# Current-LoadSwitches_3V3.net
KiCad netlist of a schematic drawn in Altium Designer
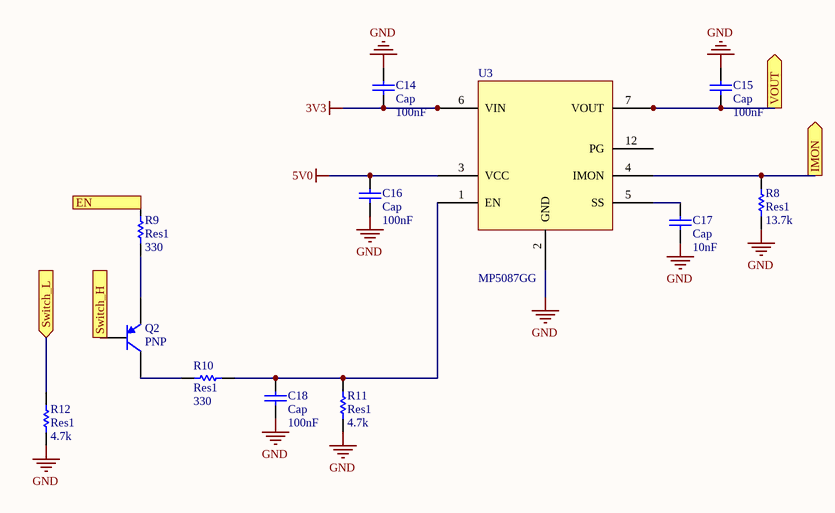
[diagram p0: Current-LoadSwitches 3V3.SchDoc]

(export (version "E")
  (design (tool "Eeschema 10.0.6"))
  (components
    (comp (ref "C14")
      (value "Cap")
      (footprint "1608[0603]")
      (description "Capacitor")
      (fields (field (name "ALTIUM_VALUE") "100nF") (field (name "PUBLISHER") "Altium Limited"))
      (libsource (lib "Miscellaneous Devices") (part "Cap"))
    )
    (comp (ref "C15")
      (value "Cap")
      (footprint "1608[0603]")
      (description "Capacitor")
      (fields (field (name "ALTIUM_VALUE") "100nF") (field (name "PUBLISHER") "Altium Limited"))
      (libsource (lib "Miscellaneous Devices") (part "Cap"))
    )
    (comp (ref "C16")
      (value "Cap")
      (footprint "1608[0603]")
      (description "Capacitor")
      (fields (field (name "ALTIUM_VALUE") "100nF") (field (name "PUBLISHER") "Altium Limited"))
      (libsource (lib "Miscellaneous Devices") (part "Cap"))
    )
    (comp (ref "C17")
      (value "Cap")
      (footprint "1608[0603]")
      (description "Capacitor")
      (fields (field (name "ALTIUM_VALUE") "10nF") (field (name "PUBLISHER") "Altium Limited"))
      (libsource (lib "Miscellaneous Devices") (part "Cap"))
    )
    (comp (ref "C18")
      (value "Cap")
      (footprint "1608[0603]")
      (description "Capacitor")
      (fields (field (name "ALTIUM_VALUE") "100nF") (field (name "PUBLISHER") "Altium Limited"))
      (libsource (lib "Miscellaneous Devices") (part "Cap"))
    )
    (comp (ref "Q2")
      (value "PNP")
      (footprint "SOT-23B_N")
      (description "PNP Bipolar Transistor")
      (fields (field (name "PUBLISHER") "Altium Limited"))
      (libsource (lib "Miscellaneous Devices") (part "PNP"))
    )
    (comp (ref "R8")
      (value "Res1")
      (footprint "1608[0603]")
      (description "Resistor")
      (fields (field (name "ALTIUM_VALUE") "13.7k") (field (name "PUBLISHER") "Altium Limited"))
      (libsource (lib "Miscellaneous Devices") (part "Res1"))
    )
    (comp (ref "R9")
      (value "Res1")
      (footprint "1608[0603]")
      (description "Resistor")
      (fields (field (name "ALTIUM_VALUE") "330") (field (name "PUBLISHER") "Altium Limited"))
      (libsource (lib "Miscellaneous Devices") (part "Res1"))
    )
    (comp (ref "R10")
      (value "Res1")
      (footprint "1608[0603]")
      (description "Resistor")
      (fields (field (name "ALTIUM_VALUE") "330") (field (name "PUBLISHER") "Altium Limited"))
      (libsource (lib "Miscellaneous Devices") (part "Res1"))
    )
    (comp (ref "R11")
      (value "Res1")
      (footprint "1608[0603]")
      (description "Resistor")
      (fields (field (name "ALTIUM_VALUE") "4.7k") (field (name "PUBLISHER") "Altium Limited"))
      (libsource (lib "Miscellaneous Devices") (part "Res1"))
    )
    (comp (ref "R12")
      (value "Res1")
      (footprint "1608[0603]")
      (description "Resistor")
      (fields (field (name "ALTIUM_VALUE") "4.7k") (field (name "PUBLISHER") "Altium Limited"))
      (libsource (lib "Miscellaneous Devices") (part "Res1"))
    )
    (comp (ref "U3")
      (value "MP5087GG")
      (footprint "MP5087GG-Z")
      (libsource (lib "MP5087GG-Z") (part "Component_1"))
    )
  )
  (nets
    (net (code "1") (name "/EN") (class "Default")
      (node (ref "R9") (pin "2") (pinfunction "2_2") (pintype "passive"))
    )
    (net (code "2") (name "/IMON") (class "Default")
      (node (ref "R8") (pin "2") (pinfunction "2_2") (pintype "passive"))
      (node (ref "U3") (pin "4") (pinfunction "IMON_4") (pintype "passive"))
    )
    (net (code "3") (name "/Switch_H") (class "Default")
      (node (ref "Q2") (pin "2") (pinfunction "B_2") (pintype "passive"))
    )
    (net (code "4") (name "/Switch_L") (class "Default")
      (node (ref "R12") (pin "2") (pinfunction "2_2") (pintype "passive"))
    )
    (net (code "5") (name "/VOUT") (class "Default")
      (node (ref "C15") (pin "1") (pinfunction "1_1") (pintype "passive"))
      (node (ref "U3") (pin "10") (pinfunction "VOUT_10") (pintype "passive"))
      (node (ref "U3") (pin "7") (pinfunction "VOUT_7") (pintype "passive"))
      (node (ref "U3") (pin "8") (pinfunction "VOUT_8") (pintype "passive"))
      (node (ref "U3") (pin "9") (pinfunction "VOUT_9") (pintype "passive"))
    )
    (net (code "6") (name "3V3") (class "Default")
      (node (ref "C14") (pin "1") (pinfunction "1_1") (pintype "passive"))
      (node (ref "U3") (pin "11") (pinfunction "VOUT_11") (pintype "passive"))
      (node (ref "U3") (pin "6") (pinfunction "VIN_6") (pintype "passive"))
    )
    (net (code "7") (name "5V0") (class "Default")
      (node (ref "C16") (pin "2") (pinfunction "2_2") (pintype "passive"))
      (node (ref "U3") (pin "3") (pinfunction "VCC_3") (pintype "passive"))
    )
    (net (code "8") (name "GND") (class "Default")
      (node (ref "C14") (pin "2") (pinfunction "2_2") (pintype "passive"))
      (node (ref "C15") (pin "2") (pinfunction "2_2") (pintype "passive"))
      (node (ref "C16") (pin "1") (pinfunction "1_1") (pintype "passive"))
      (node (ref "C17") (pin "1") (pinfunction "1_1") (pintype "passive"))
      (node (ref "C18") (pin "1") (pinfunction "1_1") (pintype "passive"))
      (node (ref "R11") (pin "1") (pinfunction "1_1") (pintype "passive"))
      (node (ref "R12") (pin "1") (pinfunction "1_1") (pintype "passive"))
      (node (ref "R8") (pin "1") (pinfunction "1_1") (pintype "passive"))
      (node (ref "U3") (pin "2") (pinfunction "GND_2") (pintype "passive"))
    )
    (net (code "9") (name "Net-(Q2-C)") (class "Default")
      (node (ref "Q2") (pin "1") (pinfunction "C_1") (pintype "passive"))
      (node (ref "R10") (pin "1") (pinfunction "1_1") (pintype "passive"))
    )
    (net (code "10") (name "Net-(Q2-E)") (class "Default")
      (node (ref "Q2") (pin "3") (pinfunction "E_3") (pintype "passive"))
      (node (ref "R9") (pin "1") (pinfunction "1_1") (pintype "passive"))
    )
    (net (code "11") (name "Net-(U3-EN)") (class "Default")
      (node (ref "C18") (pin "2") (pinfunction "2_2") (pintype "passive"))
      (node (ref "R10") (pin "2") (pinfunction "2_2") (pintype "passive"))
      (node (ref "R11") (pin "2") (pinfunction "2_2") (pintype "passive"))
      (node (ref "U3") (pin "1") (pinfunction "EN_1") (pintype "passive"))
    )
    (net (code "12") (name "Net-(U3-SS)") (class "Default")
      (node (ref "C17") (pin "2") (pinfunction "2_2") (pintype "passive"))
      (node (ref "U3") (pin "5") (pinfunction "SS_5") (pintype "passive"))
    )
    (net (code "13") (name "unconnected-(U3-PG-Pad12)") (class "Default")
      (node (ref "U3") (pin "12") (pinfunction "PG_12") (pintype "passive"))
    )
  )
)
